# schematic.net
KiCad netlist of a schematic drawn in EAGLE
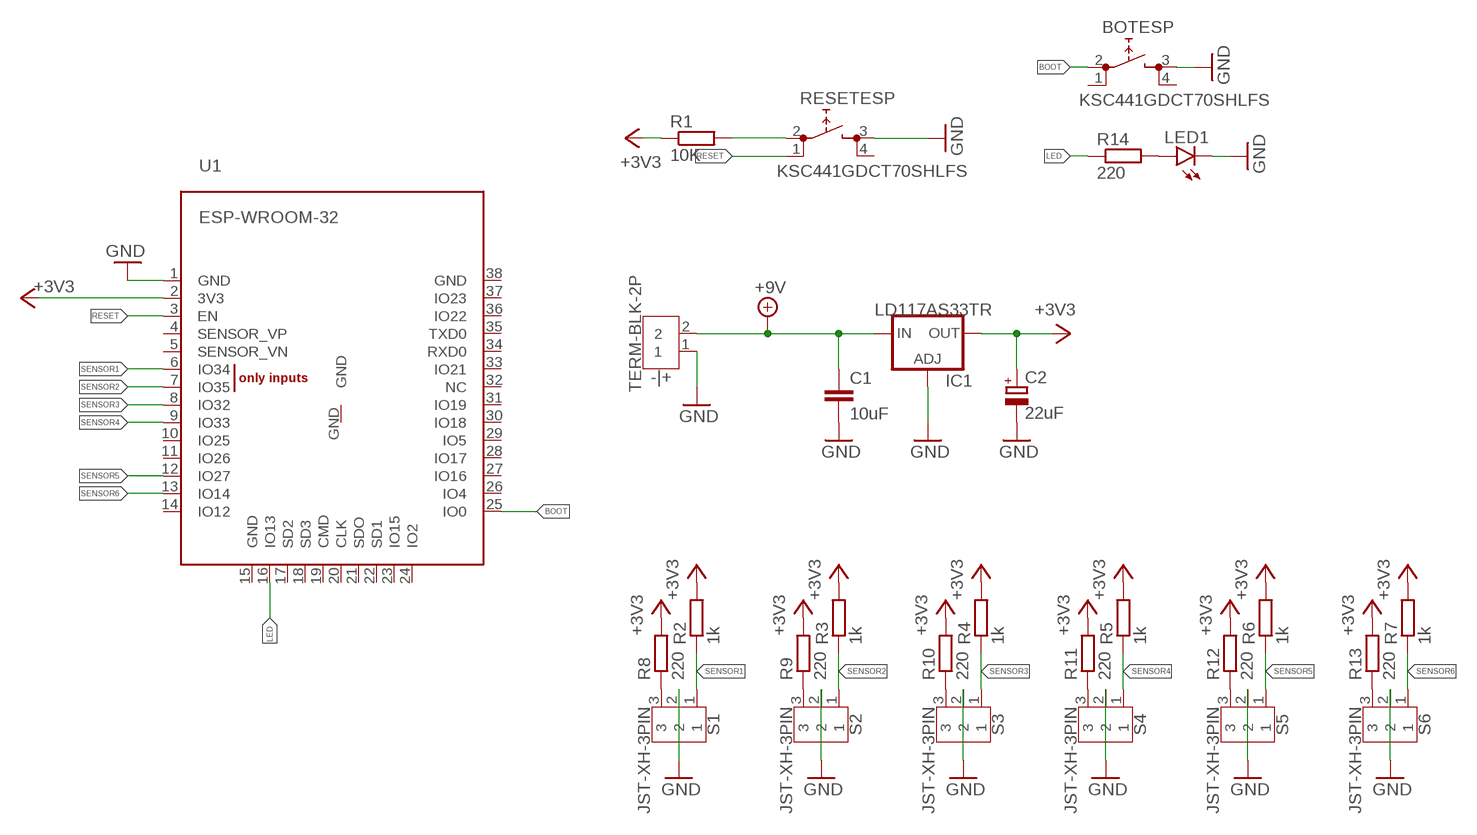
[diagram p0: schematic, sheet 1]

(export (version "E")
  (design (tool "Eeschema 10.0.6"))
  (components
    (comp (ref "-|+")
      (value "TERM-BLK-2P")
      (footprint "eagle-import:TERMBLK_254-2N")
      (fields (field (name "MANUFACTURER") "TE Connectivity AMP Connectors") (field (name "MPN") "282834-2 "))
      (libsource (lib "eagle-import") (part "2828XX-2282834-2"))
    )
    (comp (ref "BOTESP")
      (value "KSC441GDCT70SHLFS")
      (footprint "eagle-import:KSC441GDCT70SHLFS")
      (fields
        (field (name "DIGIKEY_PARTNO") "CKN12187TR-ND")
        (field (name "MANUFACTURER") "C&K")
        (field (name "MPN") "KSC441G DCT 70SH LFS")
        (field (name "CREATED_BY") "PCBLayout.com")
      )
      (libsource (lib "eagle-import") (part "KSC441GDCT70SHLFS"))
    )
    (comp (ref "C1")
      (value "10uF")
      (footprint "eagle-import:C0805")
      (libsource (lib "eagle-import") (part "C-EUC0805"))
    )
    (comp (ref "C2")
      (value "22uF")
      (footprint "eagle-import:SMC_B")
      (libsource (lib "eagle-import") (part "CPOL-EUSMCB"))
    )
    (comp (ref "IC1")
      (value "LD117AS33TR")
      (footprint "eagle-import:SOT223")
      (libsource (lib "eagle-import") (part "LD117A?S33TR"))
    )
    (comp (ref "LED1")
      (value "LEDCHIP-LED0805")
      (footprint "eagle-import:CHIP-LED0805")
      (libsource (lib "eagle-import") (part "LEDCHIP-LED0805"))
    )
    (comp (ref "R1")
      (value "10K")
      (footprint "eagle-import:R0805")
      (libsource (lib "eagle-import") (part "R-EU_R0805"))
    )
    (comp (ref "R2")
      (value "1k")
      (footprint "eagle-import:R0805")
      (libsource (lib "eagle-import") (part "R-EU_R0805"))
    )
    (comp (ref "R3")
      (value "1k")
      (footprint "eagle-import:R0805")
      (libsource (lib "eagle-import") (part "R-EU_R0805"))
    )
    (comp (ref "R4")
      (value "1k")
      (footprint "eagle-import:R0805")
      (libsource (lib "eagle-import") (part "R-EU_R0805"))
    )
    (comp (ref "R5")
      (value "1k")
      (footprint "eagle-import:R0805")
      (libsource (lib "eagle-import") (part "R-EU_R0805"))
    )
    (comp (ref "R6")
      (value "1k")
      (footprint "eagle-import:R0805")
      (libsource (lib "eagle-import") (part "R-EU_R0805"))
    )
    (comp (ref "R7")
      (value "1k")
      (footprint "eagle-import:R0805")
      (libsource (lib "eagle-import") (part "R-EU_R0805"))
    )
    (comp (ref "R8")
      (value "220")
      (footprint "eagle-import:R0805")
      (libsource (lib "eagle-import") (part "R-EU_R0805"))
    )
    (comp (ref "R9")
      (value "220")
      (footprint "eagle-import:R0805")
      (libsource (lib "eagle-import") (part "R-EU_R0805"))
    )
    (comp (ref "R10")
      (value "220")
      (footprint "eagle-import:R0805")
      (libsource (lib "eagle-import") (part "R-EU_R0805"))
    )
    (comp (ref "R11")
      (value "220")
      (footprint "eagle-import:R0805")
      (libsource (lib "eagle-import") (part "R-EU_R0805"))
    )
    (comp (ref "R12")
      (value "220")
      (footprint "eagle-import:R0805")
      (libsource (lib "eagle-import") (part "R-EU_R0805"))
    )
    (comp (ref "R13")
      (value "220")
      (footprint "eagle-import:R0805")
      (libsource (lib "eagle-import") (part "R-EU_R0805"))
    )
    (comp (ref "R14")
      (value "220")
      (footprint "eagle-import:R0805")
      (libsource (lib "eagle-import") (part "R-EU_R0805"))
    )
    (comp (ref "RESETESP")
      (value "KSC441GDCT70SHLFS")
      (footprint "eagle-import:KSC441GDCT70SHLFS")
      (fields
        (field (name "DIGIKEY_PARTNO") "CKN12187TR-ND")
        (field (name "MANUFACTURER") "C&K")
        (field (name "MPN") "KSC441G DCT 70SH LFS")
        (field (name "CREATED_BY") "PCBLayout.com")
      )
      (libsource (lib "eagle-import") (part "KSC441GDCT70SHLFS"))
    )
    (comp (ref "S1")
      (value "JST-XH-3PIN")
      (footprint "eagle-import:B3B-XH-A")
      (fields (field (name "MANUFACTURER") "JST Sales America Inc. ") (field (name "MPN") "B3B-XH-A(LF)(SN)"))
      (libsource (lib "eagle-import") (part "B3B-XH-A"))
    )
    (comp (ref "S2")
      (value "JST-XH-3PIN")
      (footprint "eagle-import:B3B-XH-A")
      (fields (field (name "MANUFACTURER") "JST Sales America Inc. ") (field (name "MPN") "B3B-XH-A(LF)(SN)"))
      (libsource (lib "eagle-import") (part "B3B-XH-A"))
    )
    (comp (ref "S3")
      (value "JST-XH-3PIN")
      (footprint "eagle-import:B3B-XH-A")
      (fields (field (name "MANUFACTURER") "JST Sales America Inc. ") (field (name "MPN") "B3B-XH-A(LF)(SN)"))
      (libsource (lib "eagle-import") (part "B3B-XH-A"))
    )
    (comp (ref "S4")
      (value "JST-XH-3PIN")
      (footprint "eagle-import:B3B-XH-A")
      (fields (field (name "MANUFACTURER") "JST Sales America Inc. ") (field (name "MPN") "B3B-XH-A(LF)(SN)"))
      (libsource (lib "eagle-import") (part "B3B-XH-A"))
    )
    (comp (ref "S5")
      (value "JST-XH-3PIN")
      (footprint "eagle-import:B3B-XH-A")
      (fields (field (name "MANUFACTURER") "JST Sales America Inc. ") (field (name "MPN") "B3B-XH-A(LF)(SN)"))
      (libsource (lib "eagle-import") (part "B3B-XH-A"))
    )
    (comp (ref "S6")
      (value "JST-XH-3PIN")
      (footprint "eagle-import:B3B-XH-A")
      (fields (field (name "MANUFACTURER") "JST Sales America Inc. ") (field (name "MPN") "B3B-XH-A(LF)(SN)"))
      (libsource (lib "eagle-import") (part "B3B-XH-A"))
    )
    (comp (ref "U1")
      (value "ESP-WROOM-32")
      (footprint "eagle-import:ESP-WROOM-32")
      (libsource (lib "eagle-import") (part "ESP-WROOM-32"))
    )
  )
  (nets
    (net (code "1") (name "+3V3") (class "Default")
      (node (ref "C2") (pin "+") (pinfunction "+_+") (pintype "passive"))
      (node (ref "IC1") (pin "4") (pinfunction "OUT_4") (pintype "passive"))
      (node (ref "R1") (pin "1") (pinfunction "1_1") (pintype "passive"))
      (node (ref "R10") (pin "2") (pinfunction "2_2") (pintype "passive"))
      (node (ref "R11") (pin "2") (pinfunction "2_2") (pintype "passive"))
      (node (ref "R12") (pin "2") (pinfunction "2_2") (pintype "passive"))
      (node (ref "R13") (pin "2") (pinfunction "2_2") (pintype "passive"))
      (node (ref "R2") (pin "2") (pinfunction "2_2") (pintype "passive"))
      (node (ref "R3") (pin "2") (pinfunction "2_2") (pintype "passive"))
      (node (ref "R4") (pin "2") (pinfunction "2_2") (pintype "passive"))
      (node (ref "R5") (pin "2") (pinfunction "2_2") (pintype "passive"))
      (node (ref "R6") (pin "2") (pinfunction "2_2") (pintype "passive"))
      (node (ref "R7") (pin "2") (pinfunction "2_2") (pintype "passive"))
      (node (ref "R8") (pin "2") (pinfunction "2_2") (pintype "passive"))
      (node (ref "R9") (pin "2") (pinfunction "2_2") (pintype "passive"))
      (node (ref "U1") (pin "2") (pinfunction "3V3_2") (pintype "bidirectional"))
    )
    (net (code "2") (name "+9V") (class "Default")
      (node (ref "-|+") (pin "2") (pinfunction "2_2") (pintype "bidirectional"))
      (node (ref "C1") (pin "1") (pinfunction "1_1") (pintype "passive"))
      (node (ref "IC1") (pin "3") (pinfunction "IN_3") (pintype "input"))
    )
    (net (code "3") (name "BOOT") (class "Default")
      (node (ref "BOTESP") (pin "2") (pinfunction "1_2") (pintype "passive"))
      (node (ref "U1") (pin "25") (pinfunction "IO0_25") (pintype "bidirectional"))
    )
    (net (code "4") (name "GND") (class "Default")
      (node (ref "-|+") (pin "1") (pinfunction "1_1") (pintype "bidirectional"))
      (node (ref "BOTESP") (pin "3") (pinfunction "3_3") (pintype "passive"))
      (node (ref "C1") (pin "2") (pinfunction "2_2") (pintype "passive"))
      (node (ref "C2") (pin "-") (pinfunction "-_-") (pintype "passive"))
      (node (ref "IC1") (pin "1") (pinfunction "ADJ_1") (pintype "input"))
      (node (ref "LED1") (pin "C") (pinfunction "C_C") (pintype "passive"))
      (node (ref "RESETESP") (pin "3") (pinfunction "3_3") (pintype "passive"))
      (node (ref "S1") (pin "2") (pinfunction "2_2") (pintype "bidirectional"))
      (node (ref "S2") (pin "2") (pinfunction "2_2") (pintype "bidirectional"))
      (node (ref "S3") (pin "2") (pinfunction "2_2") (pintype "bidirectional"))
      (node (ref "S4") (pin "2") (pinfunction "2_2") (pintype "bidirectional"))
      (node (ref "S5") (pin "2") (pinfunction "2_2") (pintype "bidirectional"))
      (node (ref "S6") (pin "2") (pinfunction "2_2") (pintype "bidirectional"))
      (node (ref "U1") (pin "1") (pinfunction "GND_1") (pintype "bidirectional"))
    )
    (net (code "5") (name "LED") (class "Default")
      (node (ref "R14") (pin "1") (pinfunction "1_1") (pintype "passive"))
      (node (ref "U1") (pin "16") (pinfunction "IO13_16") (pintype "bidirectional"))
    )
    (net (code "6") (name "Net-(LED1-PadA)") (class "Default")
      (node (ref "LED1") (pin "A") (pinfunction "A_A") (pintype "passive"))
      (node (ref "R14") (pin "2") (pinfunction "2_2") (pintype "passive"))
    )
    (net (code "7") (name "Net-(R8-Pad1)") (class "Default")
      (node (ref "R8") (pin "1") (pinfunction "1_1") (pintype "passive"))
      (node (ref "S1") (pin "3") (pinfunction "3_3") (pintype "bidirectional"))
    )
    (net (code "8") (name "Net-(R9-Pad1)") (class "Default")
      (node (ref "R9") (pin "1") (pinfunction "1_1") (pintype "passive"))
      (node (ref "S2") (pin "3") (pinfunction "3_3") (pintype "bidirectional"))
    )
    (net (code "9") (name "Net-(R10-Pad1)") (class "Default")
      (node (ref "R10") (pin "1") (pinfunction "1_1") (pintype "passive"))
      (node (ref "S3") (pin "3") (pinfunction "3_3") (pintype "bidirectional"))
    )
    (net (code "10") (name "Net-(R11-Pad1)") (class "Default")
      (node (ref "R11") (pin "1") (pinfunction "1_1") (pintype "passive"))
      (node (ref "S4") (pin "3") (pinfunction "3_3") (pintype "bidirectional"))
    )
    (net (code "11") (name "Net-(R12-Pad1)") (class "Default")
      (node (ref "R12") (pin "1") (pinfunction "1_1") (pintype "passive"))
      (node (ref "S5") (pin "3") (pinfunction "3_3") (pintype "bidirectional"))
    )
    (net (code "12") (name "Net-(R13-Pad1)") (class "Default")
      (node (ref "R13") (pin "1") (pinfunction "1_1") (pintype "passive"))
      (node (ref "S6") (pin "3") (pinfunction "3_3") (pintype "bidirectional"))
    )
    (net (code "13") (name "Net-(RESETESP-1)") (class "Default")
      (node (ref "R1") (pin "2") (pinfunction "2_2") (pintype "passive"))
      (node (ref "RESETESP") (pin "2") (pinfunction "1_2") (pintype "passive"))
    )
    (net (code "14") (name "RESET") (class "Default")
      (node (ref "RESETESP") (pin "1") (pinfunction "2_1") (pintype "passive"))
      (node (ref "U1") (pin "3") (pinfunction "EN_3") (pintype "bidirectional"))
    )
    (net (code "15") (name "SENSOR1") (class "Default")
      (node (ref "R2") (pin "1") (pinfunction "1_1") (pintype "passive"))
      (node (ref "S1") (pin "1") (pinfunction "1_1") (pintype "bidirectional"))
      (node (ref "U1") (pin "6") (pinfunction "IO34_6") (pintype "input"))
    )
    (net (code "16") (name "SENSOR2") (class "Default")
      (node (ref "R3") (pin "1") (pinfunction "1_1") (pintype "passive"))
      (node (ref "S2") (pin "1") (pinfunction "1_1") (pintype "bidirectional"))
      (node (ref "U1") (pin "7") (pinfunction "IO35_7") (pintype "input"))
    )
    (net (code "17") (name "SENSOR3") (class "Default")
      (node (ref "R4") (pin "1") (pinfunction "1_1") (pintype "passive"))
      (node (ref "S3") (pin "1") (pinfunction "1_1") (pintype "bidirectional"))
      (node (ref "U1") (pin "8") (pinfunction "IO32_8") (pintype "bidirectional"))
    )
    (net (code "18") (name "SENSOR4") (class "Default")
      (node (ref "R5") (pin "1") (pinfunction "1_1") (pintype "passive"))
      (node (ref "S4") (pin "1") (pinfunction "1_1") (pintype "bidirectional"))
      (node (ref "U1") (pin "9") (pinfunction "IO33_9") (pintype "bidirectional"))
    )
    (net (code "19") (name "SENSOR5") (class "Default")
      (node (ref "R6") (pin "1") (pinfunction "1_1") (pintype "passive"))
      (node (ref "S5") (pin "1") (pinfunction "1_1") (pintype "bidirectional"))
      (node (ref "U1") (pin "12") (pinfunction "IO27_12") (pintype "bidirectional"))
    )
    (net (code "20") (name "SENSOR6") (class "Default")
      (node (ref "R7") (pin "1") (pinfunction "1_1") (pintype "passive"))
      (node (ref "S6") (pin "1") (pinfunction "1_1") (pintype "bidirectional"))
      (node (ref "U1") (pin "13") (pinfunction "IO14_13") (pintype "bidirectional"))
    )
    (net (code "21") (name "unconnected-(BOTESP-2-Pad1)") (class "Default")
      (node (ref "BOTESP") (pin "1") (pinfunction "2_1") (pintype "passive"))
    )
    (net (code "22") (name "unconnected-(BOTESP-Pad4)") (class "Default")
      (node (ref "BOTESP") (pin "4") (pinfunction "4_4") (pintype "passive"))
    )
    (net (code "23") (name "unconnected-(RESETESP-Pad4)") (class "Default")
      (node (ref "RESETESP") (pin "4") (pinfunction "4_4") (pintype "passive"))
    )
    (net (code "24") (name "unconnected-(U1-CLK-Pad20)") (class "Default")
      (node (ref "U1") (pin "20") (pinfunction "CLK_20") (pintype "bidirectional"))
    )
    (net (code "25") (name "unconnected-(U1-CMD-Pad19)") (class "Default")
      (node (ref "U1") (pin "19") (pinfunction "CMD_19") (pintype "bidirectional"))
    )
    (net (code "26") (name "unconnected-(U1-GND-Pad15)") (class "Default")
      (node (ref "U1") (pin "15") (pinfunction "GND_15") (pintype "bidirectional"))
    )
    (net (code "27") (name "unconnected-(U1-GND-Pad38)") (class "Default")
      (node (ref "U1") (pin "38") (pinfunction "GND_38") (pintype "bidirectional"))
    )
    (net (code "28") (name "unconnected-(U1-IO2-Pad24)") (class "Default")
      (node (ref "U1") (pin "24") (pinfunction "IO2_24") (pintype "bidirectional"))
    )
    (net (code "29") (name "unconnected-(U1-IO4-Pad26)") (class "Default")
      (node (ref "U1") (pin "26") (pinfunction "IO4_26") (pintype "bidirectional"))
    )
    (net (code "30") (name "unconnected-(U1-IO5-Pad29)") (class "Default")
      (node (ref "U1") (pin "29") (pinfunction "IO5_29") (pintype "bidirectional"))
    )
    (net (code "31") (name "unconnected-(U1-IO12-Pad14)") (class "Default")
      (node (ref "U1") (pin "14") (pinfunction "IO12_14") (pintype "bidirectional"))
    )
    (net (code "32") (name "unconnected-(U1-IO15-Pad23)") (class "Default")
      (node (ref "U1") (pin "23") (pinfunction "IO15_23") (pintype "bidirectional"))
    )
    (net (code "33") (name "unconnected-(U1-IO16-Pad27)") (class "Default")
      (node (ref "U1") (pin "27") (pinfunction "IO16_27") (pintype "bidirectional"))
    )
    (net (code "34") (name "unconnected-(U1-IO17-Pad28)") (class "Default")
      (node (ref "U1") (pin "28") (pinfunction "IO17_28") (pintype "bidirectional"))
    )
    (net (code "35") (name "unconnected-(U1-IO18-Pad30)") (class "Default")
      (node (ref "U1") (pin "30") (pinfunction "IO18_30") (pintype "bidirectional"))
    )
    (net (code "36") (name "unconnected-(U1-IO19-Pad31)") (class "Default")
      (node (ref "U1") (pin "31") (pinfunction "IO19_31") (pintype "bidirectional"))
    )
    (net (code "37") (name "unconnected-(U1-IO21-Pad33)") (class "Default")
      (node (ref "U1") (pin "33") (pinfunction "IO21_33") (pintype "bidirectional"))
    )
    (net (code "38") (name "unconnected-(U1-IO22-Pad36)") (class "Default")
      (node (ref "U1") (pin "36") (pinfunction "IO22_36") (pintype "bidirectional"))
    )
    (net (code "39") (name "unconnected-(U1-IO23-Pad37)") (class "Default")
      (node (ref "U1") (pin "37") (pinfunction "IO23_37") (pintype "bidirectional"))
    )
    (net (code "40") (name "unconnected-(U1-IO25-Pad10)") (class "Default")
      (node (ref "U1") (pin "10") (pinfunction "IO25_10") (pintype "bidirectional"))
    )
    (net (code "41") (name "unconnected-(U1-IO26-Pad11)") (class "Default")
      (node (ref "U1") (pin "11") (pinfunction "IO26_11") (pintype "bidirectional"))
    )
    (net (code "42") (name "unconnected-(U1-NC-Pad32)") (class "Default")
      (node (ref "U1") (pin "32") (pinfunction "NC_32") (pintype "bidirectional"))
    )
    (net (code "43") (name "unconnected-(U1-PadGND)") (class "Default")
      (node (ref "U1") (pin "GND") (pinfunction "GND_GND") (pintype "bidirectional"))
    )
    (net (code "44") (name "unconnected-(U1-RXD0-Pad34)") (class "Default")
      (node (ref "U1") (pin "34") (pinfunction "RXD0_34") (pintype "bidirectional"))
    )
    (net (code "45") (name "unconnected-(U1-SD1-Pad22)") (class "Default")
      (node (ref "U1") (pin "22") (pinfunction "SD1_22") (pintype "bidirectional"))
    )
    (net (code "46") (name "unconnected-(U1-SD2-Pad17)") (class "Default")
      (node (ref "U1") (pin "17") (pinfunction "SD2_17") (pintype "bidirectional"))
    )
    (net (code "47") (name "unconnected-(U1-SD3-Pad18)") (class "Default")
      (node (ref "U1") (pin "18") (pinfunction "SD3_18") (pintype "bidirectional"))
    )
    (net (code "48") (name "unconnected-(U1-SDO-Pad21)") (class "Default")
      (node (ref "U1") (pin "21") (pinfunction "SDO_21") (pintype "bidirectional"))
    )
    (net (code "49") (name "unconnected-(U1-SENSOR_VN-Pad5)") (class "Default")
      (node (ref "U1") (pin "5") (pinfunction "SENSOR_VN_5") (pintype "input"))
    )
    (net (code "50") (name "unconnected-(U1-SENSOR_VP-Pad4)") (class "Default")
      (node (ref "U1") (pin "4") (pinfunction "SENSOR_VP_4") (pintype "input"))
    )
    (net (code "51") (name "unconnected-(U1-TXD0-Pad35)") (class "Default")
      (node (ref "U1") (pin "35") (pinfunction "TXD0_35") (pintype "bidirectional"))
    )
  )
)
